# teensyShield1_6_alt.net
KiCad netlist of a schematic drawn in EAGLE
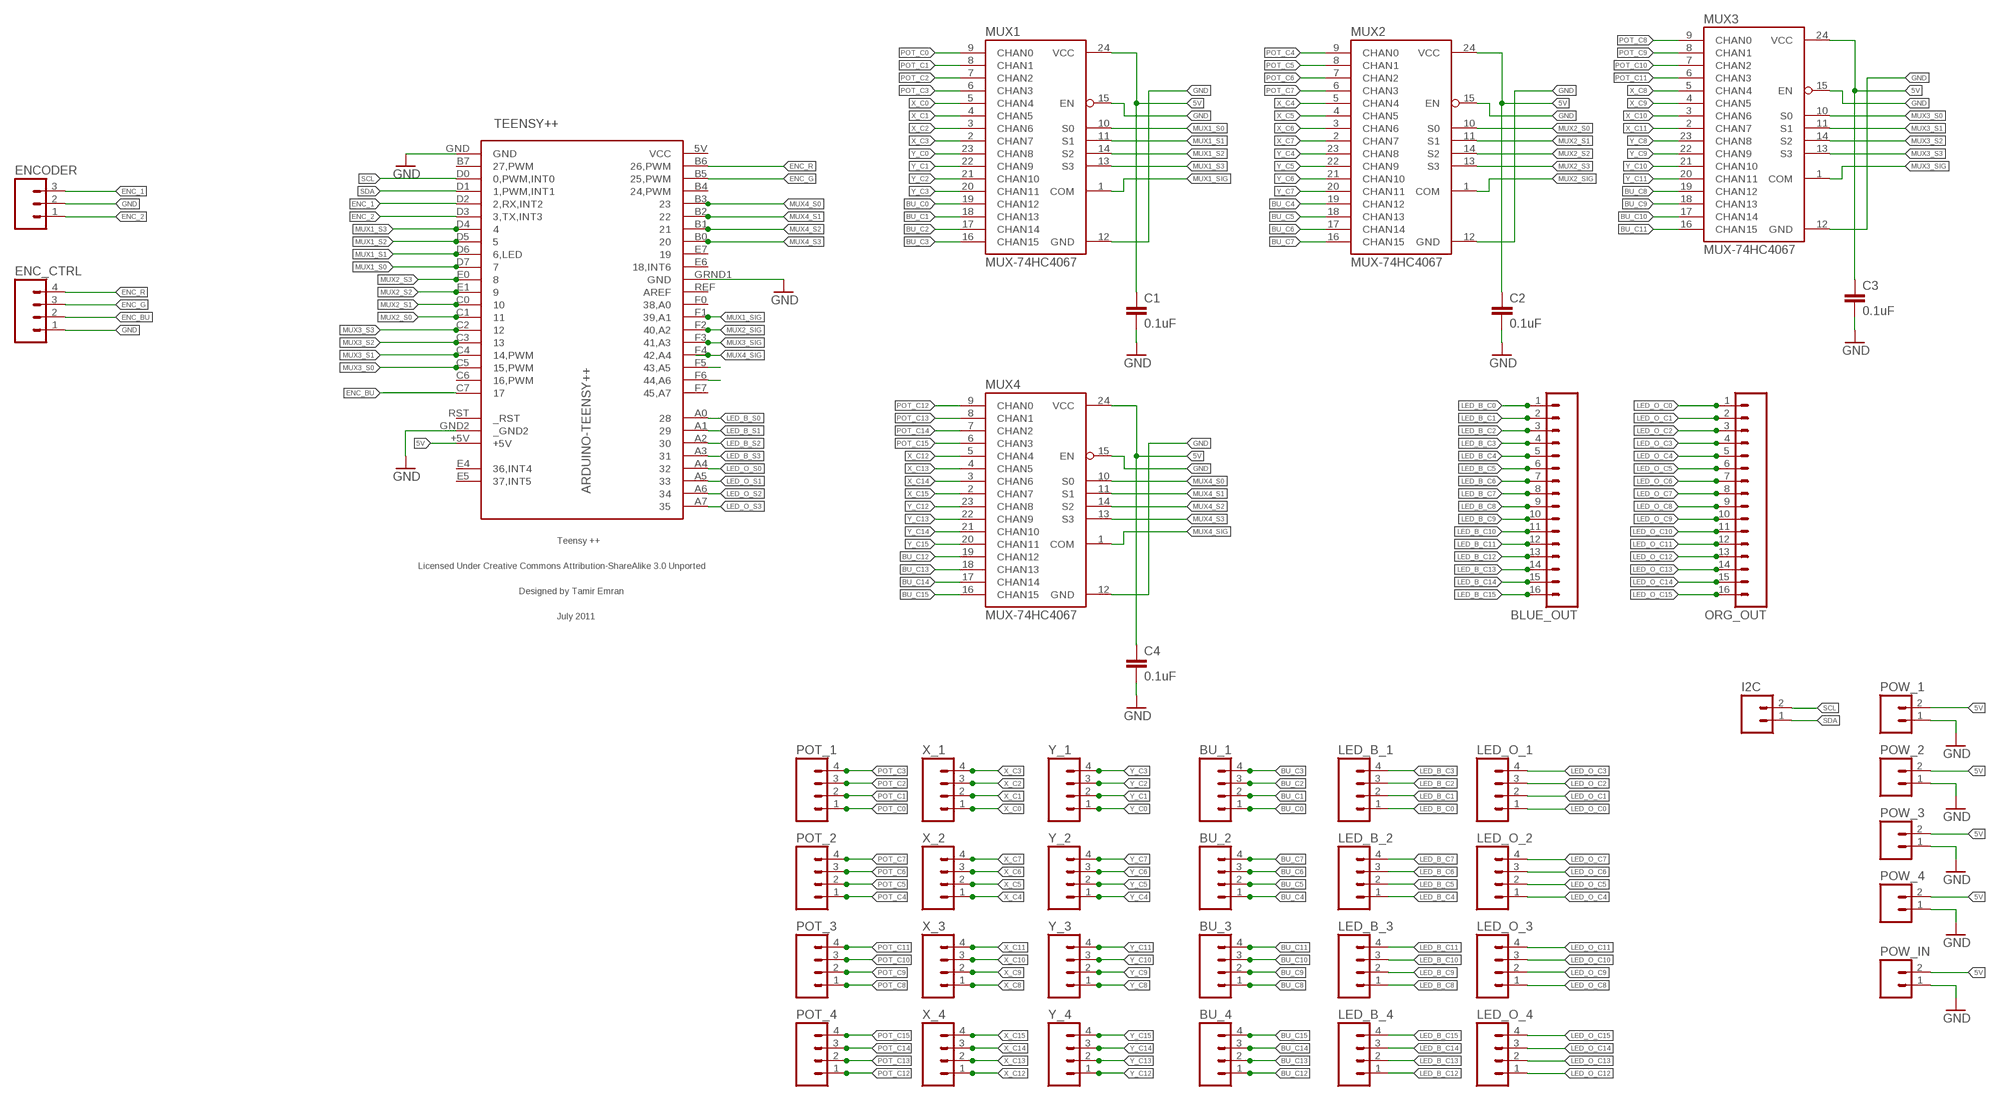
[diagram p0: schematic, sheet 1]

(export (version "E")
  (design (tool "Eeschema 10.0.6"))
  (components
    (comp (ref "BLUE_OUT")
      (value "M161X16_NO_SILK")
      (footprint "eagle-import:1X16_NO_SILK")
      (libsource (lib "eagle-import") (part "M161X16_NO_SILK"))
    )
    (comp (ref "BU_1")
      (value "M04NO_SILK_ALL_ROUND")
      (footprint "eagle-import:1X04_NO_SILK_ALL_ROUND")
      (libsource (lib "eagle-import") (part "M04NO_SILK_ALL_ROUND"))
    )
    (comp (ref "BU_2")
      (value "M04NO_SILK_ALL_ROUND")
      (footprint "eagle-import:1X04_NO_SILK_ALL_ROUND")
      (libsource (lib "eagle-import") (part "M04NO_SILK_ALL_ROUND"))
    )
    (comp (ref "BU_3")
      (value "M04NO_SILK_ALL_ROUND")
      (footprint "eagle-import:1X04_NO_SILK_ALL_ROUND")
      (libsource (lib "eagle-import") (part "M04NO_SILK_ALL_ROUND"))
    )
    (comp (ref "BU_4")
      (value "M04NO_SILK_ALL_ROUND")
      (footprint "eagle-import:1X04_NO_SILK_ALL_ROUND")
      (libsource (lib "eagle-import") (part "M04NO_SILK_ALL_ROUND"))
    )
    (comp (ref "C1")
      (value "0.1uF")
      (footprint "eagle-import:0603")
      (libsource (lib "eagle-import") (part "CAP0603"))
    )
    (comp (ref "C2")
      (value "0.1uF")
      (footprint "eagle-import:0603")
      (libsource (lib "eagle-import") (part "CAP0603"))
    )
    (comp (ref "C3")
      (value "0.1uF")
      (footprint "eagle-import:0603")
      (libsource (lib "eagle-import") (part "CAP0603"))
    )
    (comp (ref "C4")
      (value "0.1uF")
      (footprint "eagle-import:0603")
      (libsource (lib "eagle-import") (part "CAP0603"))
    )
    (comp (ref "ENCODER")
      (value "M031X03_NO_SILK")
      (footprint "eagle-import:1X03_NO_SILK")
      (libsource (lib "eagle-import") (part "M031X03_NO_SILK"))
    )
    (comp (ref "ENC_CTRL")
      (value "M041X04_NO_SILK")
      (footprint "eagle-import:1X04_NO_SILK")
      (libsource (lib "eagle-import") (part "M041X04_NO_SILK"))
    )
    (comp (ref "I2C")
      (value "M02LOCK")
      (footprint "eagle-import:1X02_LOCK")
      (libsource (lib "eagle-import") (part "M02LOCK"))
    )
    (comp (ref "LED_B_1")
      (value "M04NO_SILK_ALL_ROUND")
      (footprint "eagle-import:1X04_NO_SILK_ALL_ROUND")
      (libsource (lib "eagle-import") (part "M04NO_SILK_ALL_ROUND"))
    )
    (comp (ref "LED_B_2")
      (value "M04NO_SILK_ALL_ROUND")
      (footprint "eagle-import:1X04_NO_SILK_ALL_ROUND")
      (libsource (lib "eagle-import") (part "M04NO_SILK_ALL_ROUND"))
    )
    (comp (ref "LED_B_3")
      (value "M04NO_SILK_ALL_ROUND")
      (footprint "eagle-import:1X04_NO_SILK_ALL_ROUND")
      (libsource (lib "eagle-import") (part "M04NO_SILK_ALL_ROUND"))
    )
    (comp (ref "LED_B_4")
      (value "M04NO_SILK_ALL_ROUND")
      (footprint "eagle-import:1X04_NO_SILK_ALL_ROUND")
      (libsource (lib "eagle-import") (part "M04NO_SILK_ALL_ROUND"))
    )
    (comp (ref "LED_O_1")
      (value "M04NO_SILK_ALL_ROUND")
      (footprint "eagle-import:1X04_NO_SILK_ALL_ROUND")
      (libsource (lib "eagle-import") (part "M04NO_SILK_ALL_ROUND"))
    )
    (comp (ref "LED_O_2")
      (value "M04NO_SILK_ALL_ROUND")
      (footprint "eagle-import:1X04_NO_SILK_ALL_ROUND")
      (libsource (lib "eagle-import") (part "M04NO_SILK_ALL_ROUND"))
    )
    (comp (ref "LED_O_3")
      (value "M04NO_SILK_ALL_ROUND")
      (footprint "eagle-import:1X04_NO_SILK_ALL_ROUND")
      (libsource (lib "eagle-import") (part "M04NO_SILK_ALL_ROUND"))
    )
    (comp (ref "LED_O_4")
      (value "M04NO_SILK_ALL_ROUND")
      (footprint "eagle-import:1X04_NO_SILK_ALL_ROUND")
      (libsource (lib "eagle-import") (part "M04NO_SILK_ALL_ROUND"))
    )
    (comp (ref "MUX1")
      (value "MUX-74HC4067")
      (footprint "eagle-import:SSOP24")
      (libsource (lib "eagle-import") (part "MUX-74HC4067SMD"))
    )
    (comp (ref "MUX2")
      (value "MUX-74HC4067")
      (footprint "eagle-import:SSOP24")
      (libsource (lib "eagle-import") (part "MUX-74HC4067SMD"))
    )
    (comp (ref "MUX3")
      (value "MUX-74HC4067")
      (footprint "eagle-import:SSOP24")
      (libsource (lib "eagle-import") (part "MUX-74HC4067SMD"))
    )
    (comp (ref "MUX4")
      (value "MUX-74HC4067")
      (footprint "eagle-import:SSOP24")
      (libsource (lib "eagle-import") (part "MUX-74HC4067SMD"))
    )
    (comp (ref "ORG_OUT")
      (value "M161X16_NO_SILK")
      (footprint "eagle-import:1X16_NO_SILK")
      (libsource (lib "eagle-import") (part "M161X16_NO_SILK"))
    )
    (comp (ref "POT_1")
      (value "M04NO_SILK_ALL_ROUND")
      (footprint "eagle-import:1X04_NO_SILK_ALL_ROUND")
      (libsource (lib "eagle-import") (part "M04NO_SILK_ALL_ROUND"))
    )
    (comp (ref "POT_2")
      (value "M04NO_SILK_ALL_ROUND")
      (footprint "eagle-import:1X04_NO_SILK_ALL_ROUND")
      (libsource (lib "eagle-import") (part "M04NO_SILK_ALL_ROUND"))
    )
    (comp (ref "POT_3")
      (value "M04NO_SILK_ALL_ROUND")
      (footprint "eagle-import:1X04_NO_SILK_ALL_ROUND")
      (libsource (lib "eagle-import") (part "M04NO_SILK_ALL_ROUND"))
    )
    (comp (ref "POT_4")
      (value "M04NO_SILK_ALL_ROUND")
      (footprint "eagle-import:1X04_NO_SILK_ALL_ROUND")
      (libsource (lib "eagle-import") (part "M04NO_SILK_ALL_ROUND"))
    )
    (comp (ref "POW_1")
      (value "M02POLAR")
      (footprint "eagle-import:MOLEX-1X2")
      (libsource (lib "eagle-import") (part "M02POLAR"))
    )
    (comp (ref "POW_2")
      (value "M02POLAR")
      (footprint "eagle-import:MOLEX-1X2")
      (libsource (lib "eagle-import") (part "M02POLAR"))
    )
    (comp (ref "POW_3")
      (value "M02POLAR")
      (footprint "eagle-import:MOLEX-1X2")
      (libsource (lib "eagle-import") (part "M02POLAR"))
    )
    (comp (ref "POW_4")
      (value "M02POLAR")
      (footprint "eagle-import:MOLEX-1X2")
      (libsource (lib "eagle-import") (part "M02POLAR"))
    )
    (comp (ref "POW_IN")
      (value "M02POLAR")
      (footprint "eagle-import:MOLEX-1X2")
      (libsource (lib "eagle-import") (part "M02POLAR"))
    )
    (comp (ref "TEENSY++")
      (value "ARDUINO-TEENSY++")
      (footprint "eagle-import:TEENSY++")
      (libsource (lib "eagle-import") (part "ARDUINO-TEENSY++"))
    )
    (comp (ref "X_1")
      (value "M04NO_SILK_ALL_ROUND")
      (footprint "eagle-import:1X04_NO_SILK_ALL_ROUND")
      (libsource (lib "eagle-import") (part "M04NO_SILK_ALL_ROUND"))
    )
    (comp (ref "X_2")
      (value "M04NO_SILK_ALL_ROUND")
      (footprint "eagle-import:1X04_NO_SILK_ALL_ROUND")
      (libsource (lib "eagle-import") (part "M04NO_SILK_ALL_ROUND"))
    )
    (comp (ref "X_3")
      (value "M04NO_SILK_ALL_ROUND")
      (footprint "eagle-import:1X04_NO_SILK_ALL_ROUND")
      (libsource (lib "eagle-import") (part "M04NO_SILK_ALL_ROUND"))
    )
    (comp (ref "X_4")
      (value "M04NO_SILK_ALL_ROUND")
      (footprint "eagle-import:1X04_NO_SILK_ALL_ROUND")
      (libsource (lib "eagle-import") (part "M04NO_SILK_ALL_ROUND"))
    )
    (comp (ref "Y_1")
      (value "M04NO_SILK_ALL_ROUND")
      (footprint "eagle-import:1X04_NO_SILK_ALL_ROUND")
      (libsource (lib "eagle-import") (part "M04NO_SILK_ALL_ROUND"))
    )
    (comp (ref "Y_2")
      (value "M04NO_SILK_ALL_ROUND")
      (footprint "eagle-import:1X04_NO_SILK_ALL_ROUND")
      (libsource (lib "eagle-import") (part "M04NO_SILK_ALL_ROUND"))
    )
    (comp (ref "Y_3")
      (value "M04NO_SILK_ALL_ROUND")
      (footprint "eagle-import:1X04_NO_SILK_ALL_ROUND")
      (libsource (lib "eagle-import") (part "M04NO_SILK_ALL_ROUND"))
    )
    (comp (ref "Y_4")
      (value "M04NO_SILK_ALL_ROUND")
      (footprint "eagle-import:1X04_NO_SILK_ALL_ROUND")
      (libsource (lib "eagle-import") (part "M04NO_SILK_ALL_ROUND"))
    )
  )
  (nets
    (net (code "1") (name "/VCC") (class "Default")
      (node (ref "TEENSY++") (pin "5V") (pinfunction "VCC_5V") (pintype "power_in"))
    )
    (net (code "2") (name "5V") (class "Default")
      (node (ref "C1") (pin "1") (pinfunction "1_1") (pintype "passive"))
      (node (ref "C2") (pin "1") (pinfunction "1_1") (pintype "passive"))
      (node (ref "C3") (pin "1") (pinfunction "1_1") (pintype "passive"))
      (node (ref "C4") (pin "1") (pinfunction "1_1") (pintype "passive"))
      (node (ref "MUX1") (pin "24") (pinfunction "VCC_24") (pintype "bidirectional"))
      (node (ref "MUX2") (pin "24") (pinfunction "VCC_24") (pintype "bidirectional"))
      (node (ref "MUX3") (pin "24") (pinfunction "VCC_24") (pintype "bidirectional"))
      (node (ref "MUX4") (pin "24") (pinfunction "VCC_24") (pintype "bidirectional"))
      (node (ref "POW_1") (pin "2") (pinfunction "2_2") (pintype "passive"))
      (node (ref "POW_2") (pin "2") (pinfunction "2_2") (pintype "passive"))
      (node (ref "POW_3") (pin "2") (pinfunction "2_2") (pintype "passive"))
      (node (ref "POW_4") (pin "2") (pinfunction "2_2") (pintype "passive"))
      (node (ref "POW_IN") (pin "2") (pinfunction "2_2") (pintype "passive"))
    )
    (net (code "3") (name "BU_C0") (class "Default")
      (node (ref "BU_1") (pin "1") (pinfunction "1_1") (pintype "passive"))
      (node (ref "MUX1") (pin "19") (pinfunction "CHAN12_19") (pintype "bidirectional"))
    )
    (net (code "4") (name "BU_C1") (class "Default")
      (node (ref "BU_1") (pin "2") (pinfunction "2_2") (pintype "passive"))
      (node (ref "MUX1") (pin "18") (pinfunction "CHAN13_18") (pintype "bidirectional"))
    )
    (net (code "5") (name "BU_C2") (class "Default")
      (node (ref "BU_1") (pin "3") (pinfunction "3_3") (pintype "passive"))
      (node (ref "MUX1") (pin "17") (pinfunction "CHAN14_17") (pintype "bidirectional"))
    )
    (net (code "6") (name "BU_C3") (class "Default")
      (node (ref "BU_1") (pin "4") (pinfunction "4_4") (pintype "passive"))
      (node (ref "MUX1") (pin "16") (pinfunction "CHAN15_16") (pintype "bidirectional"))
    )
    (net (code "7") (name "BU_C4") (class "Default")
      (node (ref "BU_2") (pin "1") (pinfunction "1_1") (pintype "passive"))
      (node (ref "MUX2") (pin "19") (pinfunction "CHAN12_19") (pintype "bidirectional"))
    )
    (net (code "8") (name "BU_C5") (class "Default")
      (node (ref "BU_2") (pin "2") (pinfunction "2_2") (pintype "passive"))
      (node (ref "MUX2") (pin "18") (pinfunction "CHAN13_18") (pintype "bidirectional"))
    )
    (net (code "9") (name "BU_C6") (class "Default")
      (node (ref "BU_2") (pin "3") (pinfunction "3_3") (pintype "passive"))
      (node (ref "MUX2") (pin "17") (pinfunction "CHAN14_17") (pintype "bidirectional"))
    )
    (net (code "10") (name "BU_C7") (class "Default")
      (node (ref "BU_2") (pin "4") (pinfunction "4_4") (pintype "passive"))
      (node (ref "MUX2") (pin "16") (pinfunction "CHAN15_16") (pintype "bidirectional"))
    )
    (net (code "11") (name "BU_C8") (class "Default")
      (node (ref "BU_3") (pin "1") (pinfunction "1_1") (pintype "passive"))
      (node (ref "MUX3") (pin "19") (pinfunction "CHAN12_19") (pintype "bidirectional"))
    )
    (net (code "12") (name "BU_C9") (class "Default")
      (node (ref "BU_3") (pin "2") (pinfunction "2_2") (pintype "passive"))
      (node (ref "MUX3") (pin "18") (pinfunction "CHAN13_18") (pintype "bidirectional"))
    )
    (net (code "13") (name "BU_C10") (class "Default")
      (node (ref "BU_3") (pin "3") (pinfunction "3_3") (pintype "passive"))
      (node (ref "MUX3") (pin "17") (pinfunction "CHAN14_17") (pintype "bidirectional"))
    )
    (net (code "14") (name "BU_C11") (class "Default")
      (node (ref "BU_3") (pin "4") (pinfunction "4_4") (pintype "passive"))
      (node (ref "MUX3") (pin "16") (pinfunction "CHAN15_16") (pintype "bidirectional"))
    )
    (net (code "15") (name "BU_C12") (class "Default")
      (node (ref "BU_4") (pin "1") (pinfunction "1_1") (pintype "passive"))
      (node (ref "MUX4") (pin "19") (pinfunction "CHAN12_19") (pintype "bidirectional"))
    )
    (net (code "16") (name "BU_C13") (class "Default")
      (node (ref "BU_4") (pin "2") (pinfunction "2_2") (pintype "passive"))
      (node (ref "MUX4") (pin "18") (pinfunction "CHAN13_18") (pintype "bidirectional"))
    )
    (net (code "17") (name "BU_C14") (class "Default")
      (node (ref "BU_4") (pin "3") (pinfunction "3_3") (pintype "passive"))
      (node (ref "MUX4") (pin "17") (pinfunction "CHAN14_17") (pintype "bidirectional"))
    )
    (net (code "18") (name "BU_C15") (class "Default")
      (node (ref "BU_4") (pin "4") (pinfunction "4_4") (pintype "passive"))
      (node (ref "MUX4") (pin "16") (pinfunction "CHAN15_16") (pintype "bidirectional"))
    )
    (net (code "19") (name "ENC_1") (class "Default")
      (node (ref "ENCODER") (pin "3") (pinfunction "3_3") (pintype "passive"))
      (node (ref "TEENSY++") (pin "D2") (pinfunction "2,RX,INT2_D2") (pintype "bidirectional"))
    )
    (net (code "20") (name "ENC_2") (class "Default")
      (node (ref "ENCODER") (pin "1") (pinfunction "1_1") (pintype "passive"))
      (node (ref "TEENSY++") (pin "D3") (pinfunction "3,TX,INT3_D3") (pintype "bidirectional"))
    )
    (net (code "21") (name "ENC_BU") (class "Default")
      (node (ref "ENC_CTRL") (pin "2") (pinfunction "2_2") (pintype "passive"))
      (node (ref "TEENSY++") (pin "C7") (pinfunction "17_C7") (pintype "bidirectional"))
    )
    (net (code "22") (name "ENC_G") (class "Default")
      (node (ref "ENC_CTRL") (pin "3") (pinfunction "3_3") (pintype "passive"))
      (node (ref "TEENSY++") (pin "B5") (pinfunction "25,PWM_B5") (pintype "bidirectional"))
    )
    (net (code "23") (name "ENC_R") (class "Default")
      (node (ref "ENC_CTRL") (pin "4") (pinfunction "4_4") (pintype "passive"))
      (node (ref "TEENSY++") (pin "B6") (pinfunction "26,PWM_B6") (pintype "bidirectional"))
    )
    (net (code "24") (name "GND") (class "Default")
      (node (ref "C1") (pin "2") (pinfunction "2_2") (pintype "passive"))
      (node (ref "C2") (pin "2") (pinfunction "2_2") (pintype "passive"))
      (node (ref "C3") (pin "2") (pinfunction "2_2") (pintype "passive"))
      (node (ref "C4") (pin "2") (pinfunction "2_2") (pintype "passive"))
      (node (ref "ENCODER") (pin "2") (pinfunction "2_2") (pintype "passive"))
      (node (ref "ENC_CTRL") (pin "1") (pinfunction "1_1") (pintype "passive"))
      (node (ref "MUX1") (pin "12") (pinfunction "GND_12") (pintype "bidirectional"))
      (node (ref "MUX1") (pin "15") (pinfunction "EN_15") (pintype "input"))
      (node (ref "MUX2") (pin "12") (pinfunction "GND_12") (pintype "bidirectional"))
      (node (ref "MUX2") (pin "15") (pinfunction "EN_15") (pintype "input"))
      (node (ref "MUX3") (pin "12") (pinfunction "GND_12") (pintype "bidirectional"))
      (node (ref "MUX3") (pin "15") (pinfunction "EN_15") (pintype "input"))
      (node (ref "MUX4") (pin "12") (pinfunction "GND_12") (pintype "bidirectional"))
      (node (ref "MUX4") (pin "15") (pinfunction "EN_15") (pintype "input"))
      (node (ref "POW_1") (pin "1") (pinfunction "1_1") (pintype "passive"))
      (node (ref "POW_2") (pin "1") (pinfunction "1_1") (pintype "passive"))
      (node (ref "POW_3") (pin "1") (pinfunction "1_1") (pintype "passive"))
      (node (ref "POW_4") (pin "1") (pinfunction "1_1") (pintype "passive"))
      (node (ref "POW_IN") (pin "1") (pinfunction "1_1") (pintype "passive"))
      (node (ref "TEENSY++") (pin "GND") (pinfunction "GND_GND") (pintype "power_in"))
      (node (ref "TEENSY++") (pin "GND2") (pinfunction "_GND2_GND2") (pintype "power_in"))
      (node (ref "TEENSY++") (pin "GRND1") (pinfunction "GND_GRND1") (pintype "power_in"))
    )
    (net (code "25") (name "LED_B_C0") (class "Default")
      (node (ref "BLUE_OUT") (pin "1") (pinfunction "1_1") (pintype "passive"))
      (node (ref "LED_B_1") (pin "1") (pinfunction "1_1") (pintype "passive"))
    )
    (net (code "26") (name "LED_B_C1") (class "Default")
      (node (ref "BLUE_OUT") (pin "2") (pinfunction "2_2") (pintype "passive"))
      (node (ref "LED_B_1") (pin "2") (pinfunction "2_2") (pintype "passive"))
    )
    (net (code "27") (name "LED_B_C2") (class "Default")
      (node (ref "BLUE_OUT") (pin "3") (pinfunction "3_3") (pintype "passive"))
      (node (ref "LED_B_1") (pin "3") (pinfunction "3_3") (pintype "passive"))
    )
    (net (code "28") (name "LED_B_C3") (class "Default")
      (node (ref "BLUE_OUT") (pin "4") (pinfunction "4_4") (pintype "passive"))
      (node (ref "LED_B_1") (pin "4") (pinfunction "4_4") (pintype "passive"))
    )
    (net (code "29") (name "LED_B_C4") (class "Default")
      (node (ref "BLUE_OUT") (pin "5") (pinfunction "5_5") (pintype "passive"))
      (node (ref "LED_B_2") (pin "1") (pinfunction "1_1") (pintype "passive"))
    )
    (net (code "30") (name "LED_B_C5") (class "Default")
      (node (ref "BLUE_OUT") (pin "6") (pinfunction "6_6") (pintype "passive"))
      (node (ref "LED_B_2") (pin "2") (pinfunction "2_2") (pintype "passive"))
    )
    (net (code "31") (name "LED_B_C6") (class "Default")
      (node (ref "BLUE_OUT") (pin "7") (pinfunction "7_7") (pintype "passive"))
      (node (ref "LED_B_2") (pin "3") (pinfunction "3_3") (pintype "passive"))
    )
    (net (code "32") (name "LED_B_C7") (class "Default")
      (node (ref "BLUE_OUT") (pin "8") (pinfunction "8_8") (pintype "passive"))
      (node (ref "LED_B_2") (pin "4") (pinfunction "4_4") (pintype "passive"))
    )
    (net (code "33") (name "LED_B_C8") (class "Default")
      (node (ref "BLUE_OUT") (pin "9") (pinfunction "9_9") (pintype "passive"))
      (node (ref "LED_B_3") (pin "1") (pinfunction "1_1") (pintype "passive"))
    )
    (net (code "34") (name "LED_B_C9") (class "Default")
      (node (ref "BLUE_OUT") (pin "10") (pinfunction "10_10") (pintype "passive"))
      (node (ref "LED_B_3") (pin "2") (pinfunction "2_2") (pintype "passive"))
    )
    (net (code "35") (name "LED_B_C10") (class "Default")
      (node (ref "BLUE_OUT") (pin "11") (pinfunction "11_11") (pintype "passive"))
      (node (ref "LED_B_3") (pin "3") (pinfunction "3_3") (pintype "passive"))
    )
    (net (code "36") (name "LED_B_C11") (class "Default")
      (node (ref "BLUE_OUT") (pin "12") (pinfunction "12_12") (pintype "passive"))
      (node (ref "LED_B_3") (pin "4") (pinfunction "4_4") (pintype "passive"))
    )
    (net (code "37") (name "LED_B_C12") (class "Default")
      (node (ref "BLUE_OUT") (pin "13") (pinfunction "13_13") (pintype "passive"))
      (node (ref "LED_B_4") (pin "1") (pinfunction "1_1") (pintype "passive"))
    )
    (net (code "38") (name "LED_B_C13") (class "Default")
      (node (ref "BLUE_OUT") (pin "14") (pinfunction "14_14") (pintype "passive"))
      (node (ref "LED_B_4") (pin "2") (pinfunction "2_2") (pintype "passive"))
    )
    (net (code "39") (name "LED_B_C14") (class "Default")
      (node (ref "BLUE_OUT") (pin "15") (pinfunction "15_15") (pintype "passive"))
      (node (ref "LED_B_4") (pin "3") (pinfunction "3_3") (pintype "passive"))
    )
    (net (code "40") (name "LED_B_C15") (class "Default")
      (node (ref "BLUE_OUT") (pin "16") (pinfunction "16_16") (pintype "passive"))
      (node (ref "LED_B_4") (pin "4") (pinfunction "4_4") (pintype "passive"))
    )
    (net (code "41") (name "LED_B_S0") (class "Default")
      (node (ref "TEENSY++") (pin "A0") (pinfunction "28_A0") (pintype "bidirectional"))
    )
    (net (code "42") (name "LED_B_S1") (class "Default")
      (node (ref "TEENSY++") (pin "A1") (pinfunction "29_A1") (pintype "bidirectional"))
    )
    (net (code "43") (name "LED_B_S2") (class "Default")
      (node (ref "TEENSY++") (pin "A2") (pinfunction "30_A2") (pintype "bidirectional"))
    )
    (net (code "44") (name "LED_B_S3") (class "Default")
      (node (ref "TEENSY++") (pin "A3") (pinfunction "31_A3") (pintype "bidirectional"))
    )
    (net (code "45") (name "LED_O_C0") (class "Default")
      (node (ref "LED_O_1") (pin "1") (pinfunction "1_1") (pintype "passive"))
      (node (ref "ORG_OUT") (pin "1") (pinfunction "1_1") (pintype "passive"))
    )
    (net (code "46") (name "LED_O_C1") (class "Default")
      (node (ref "LED_O_1") (pin "2") (pinfunction "2_2") (pintype "passive"))
      (node (ref "ORG_OUT") (pin "2") (pinfunction "2_2") (pintype "passive"))
    )
    (net (code "47") (name "LED_O_C2") (class "Default")
      (node (ref "LED_O_1") (pin "3") (pinfunction "3_3") (pintype "passive"))
      (node (ref "ORG_OUT") (pin "3") (pinfunction "3_3") (pintype "passive"))
    )
    (net (code "48") (name "LED_O_C3") (class "Default")
      (node (ref "LED_O_1") (pin "4") (pinfunction "4_4") (pintype "passive"))
      (node (ref "ORG_OUT") (pin "4") (pinfunction "4_4") (pintype "passive"))
    )
    (net (code "49") (name "LED_O_C4") (class "Default")
      (node (ref "LED_O_2") (pin "1") (pinfunction "1_1") (pintype "passive"))
      (node (ref "ORG_OUT") (pin "5") (pinfunction "5_5") (pintype "passive"))
    )
    (net (code "50") (name "LED_O_C5") (class "Default")
      (node (ref "LED_O_2") (pin "2") (pinfunction "2_2") (pintype "passive"))
      (node (ref "ORG_OUT") (pin "6") (pinfunction "6_6") (pintype "passive"))
    )
    (net (code "51") (name "LED_O_C6") (class "Default")
      (node (ref "LED_O_2") (pin "3") (pinfunction "3_3") (pintype "passive"))
      (node (ref "ORG_OUT") (pin "7") (pinfunction "7_7") (pintype "passive"))
    )
    (net (code "52") (name "LED_O_C7") (class "Default")
      (node (ref "LED_O_2") (pin "4") (pinfunction "4_4") (pintype "passive"))
      (node (ref "ORG_OUT") (pin "8") (pinfunction "8_8") (pintype "passive"))
    )
    (net (code "53") (name "LED_O_C8") (class "Default")
      (node (ref "LED_O_3") (pin "1") (pinfunction "1_1") (pintype "passive"))
      (node (ref "ORG_OUT") (pin "9") (pinfunction "9_9") (pintype "passive"))
    )
    (net (code "54") (name "LED_O_C9") (class "Default")
      (node (ref "LED_O_3") (pin "2") (pinfunction "2_2") (pintype "passive"))
      (node (ref "ORG_OUT") (pin "10") (pinfunction "10_10") (pintype "passive"))
    )
    (net (code "55") (name "LED_O_C10") (class "Default")
      (node (ref "LED_O_3") (pin "3") (pinfunction "3_3") (pintype "passive"))
      (node (ref "ORG_OUT") (pin "11") (pinfunction "11_11") (pintype "passive"))
    )
    (net (code "56") (name "LED_O_C11") (class "Default")
      (node (ref "LED_O_3") (pin "4") (pinfunction "4_4") (pintype "passive"))
      (node (ref "ORG_OUT") (pin "12") (pinfunction "12_12") (pintype "passive"))
    )
    (net (code "57") (name "LED_O_C12") (class "Default")
      (node (ref "LED_O_4") (pin "1") (pinfunction "1_1") (pintype "passive"))
      (node (ref "ORG_OUT") (pin "13") (pinfunction "13_13") (pintype "passive"))
    )
    (net (code "58") (name "LED_O_C13") (class "Default")
      (node (ref "LED_O_4") (pin "2") (pinfunction "2_2") (pintype "passive"))
      (node (ref "ORG_OUT") (pin "14") (pinfunction "14_14") (pintype "passive"))
    )
    (net (code "59") (name "LED_O_C14") (class "Default")
      (node (ref "LED_O_4") (pin "3") (pinfunction "3_3") (pintype "passive"))
      (node (ref "ORG_OUT") (pin "15") (pinfunction "15_15") (pintype "passive"))
    )
    (net (code "60") (name "LED_O_C15") (class "Default")
      (node (ref "LED_O_4") (pin "4") (pinfunction "4_4") (pintype "passive"))
      (node (ref "ORG_OUT") (pin "16") (pinfunction "16_16") (pintype "passive"))
    )
    (net (code "61") (name "LED_O_S0") (class "Default")
      (node (ref "TEENSY++") (pin "A4") (pinfunction "32_A4") (pintype "bidirectional"))
    )
    (net (code "62") (name "LED_O_S1") (class "Default")
      (node (ref "TEENSY++") (pin "A5") (pinfunction "33_A5") (pintype "bidirectional"))
    )
    (net (code "63") (name "LED_O_S2") (class "Default")
      (node (ref "TEENSY++") (pin "A6") (pinfunction "34_A6") (pintype "bidirectional"))
    )
    (net (code "64") (name "LED_O_S3") (class "Default")
      (node (ref "TEENSY++") (pin "A7") (pinfunction "35_A7") (pintype "bidirectional"))
    )
    (net (code "65") (name "MUX1_S0") (class "Default")
      (node (ref "MUX1") (pin "10") (pinfunction "S0_10") (pintype "input"))
      (node (ref "TEENSY++") (pin "D7") (pinfunction "7_D7") (pintype "bidirectional"))
    )
    (net (code "66") (name "MUX1_S1") (class "Default")
      (node (ref "MUX1") (pin "11") (pinfunction "S1_11") (pintype "input"))
      (node (ref "TEENSY++") (pin "D6") (pinfunction "6,LED_D6") (pintype "bidirectional"))
    )
    (net (code "67") (name "MUX1_S2") (class "Default")
      (node (ref "MUX1") (pin "14") (pinfunction "S2_14") (pintype "input"))
      (node (ref "TEENSY++") (pin "D5") (pinfunction "5_D5") (pintype "bidirectional"))
    )
    (net (code "68") (name "MUX1_S3") (class "Default")
      (node (ref "MUX1") (pin "13") (pinfunction "S3_13") (pintype "input"))
      (node (ref "TEENSY++") (pin "D4") (pinfunction "4_D4") (pintype "bidirectional"))
    )
    (net (code "69") (name "MUX1_SIG") (class "Default")
      (node (ref "MUX1") (pin "1") (pinfunction "COM_1") (pintype "bidirectional"))
    )
    (net (code "70") (name "MUX2_S0") (class "Default")
      (node (ref "MUX2") (pin "10") (pinfunction "S0_10") (pintype "input"))
      (node (ref "TEENSY++") (pin "C1") (pinfunction "11_C1") (pintype "bidirectional"))
    )
    (net (code "71") (name "MUX2_S1") (class "Default")
      (node (ref "MUX2") (pin "11") (pinfunction "S1_11") (pintype "input"))
      (node (ref "TEENSY++") (pin "C0") (pinfunction "10_C0") (pintype "bidirectional"))
    )
    (net (code "72") (name "MUX2_S2") (class "Default")
      (node (ref "MUX2") (pin "14") (pinfunction "S2_14") (pintype "input"))
      (node (ref "TEENSY++") (pin "E1") (pinfunction "9_E1") (pintype "bidirectional"))
    )
    (net (code "73") (name "MUX2_S3") (class "Default")
      (node (ref "MUX2") (pin "13") (pinfunction "S3_13") (pintype "input"))
      (node (ref "TEENSY++") (pin "E0") (pinfunction "8_E0") (pintype "bidirectional"))
    )
    (net (code "74") (name "MUX2_SIG") (class "Default")
      (node (ref "MUX2") (pin "1") (pinfunction "COM_1") (pintype "bidirectional"))
    )
    (net (code "75") (name "MUX3_S0") (class "Default")
      (node (ref "MUX3") (pin "10") (pinfunction "S0_10") (pintype "input"))
      (node (ref "TEENSY++") (pin "C5") (pinfunction "15,PWM_C5") (pintype "bidirectional"))
    )
    (net (code "76") (name "MUX3_S1") (class "Default")
      (node (ref "MUX3") (pin "11") (pinfunction "S1_11") (pintype "input"))
      (node (ref "TEENSY++") (pin "C4") (pinfunction "14,PWM_C4") (pintype "bidirectional"))
    )
    (net (code "77") (name "MUX3_S2") (class "Default")
      (node (ref "MUX3") (pin "14") (pinfunction "S2_14") (pintype "input"))
      (node (ref "TEENSY++") (pin "C3") (pinfunction "13_C3") (pintype "bidirectional"))
    )
    (net (code "78") (name "MUX3_S3") (class "Default")
      (node (ref "MUX3") (pin "13") (pinfunction "S3_13") (pintype "input"))
      (node (ref "TEENSY++") (pin "C2") (pinfunction "12_C2") (pintype "bidirectional"))
    )
    (net (code "79") (name "MUX3_SIG") (class "Default")
      (node (ref "MUX3") (pin "1") (pinfunction "COM_1") (pintype "bidirectional"))
      (node (ref "TEENSY++") (pin "F3") (pinfunction "41,A3_F3") (pintype "bidirectional"))
    )
    (net (code "80") (name "MUX4_S0") (class "Default")
      (node (ref "MUX4") (pin "10") (pinfunction "S0_10") (pintype "input"))
      (node (ref "TEENSY++") (pin "B3") (pinfunction "23_B3") (pintype "bidirectional"))
    )
    (net (code "81") (name "MUX4_S1") (class "Default")
      (node (ref "MUX4") (pin "11") (pinfunction "S1_11") (pintype "input"))
      (node (ref "TEENSY++") (pin "B2") (pinfunction "22_B2") (pintype "bidirectional"))
    )
    (net (code "82") (name "MUX4_S2") (class "Default")
      (node (ref "MUX4") (pin "14") (pinfunction "S2_14") (pintype "input"))
      (node (ref "TEENSY++") (pin "B1") (pinfunction "21_B1") (pintype "bidirectional"))
    )
    (net (code "83") (name "MUX4_S3") (class "Default")
      (node (ref "MUX4") (pin "13") (pinfunction "S3_13") (pintype "input"))
      (node (ref "TEENSY++") (pin "B0") (pinfunction "20_B0") (pintype "bidirectional"))
    )
    (net (code "84") (name "MUX4_SIG") (class "Default")
      (node (ref "MUX4") (pin "1") (pinfunction "COM_1") (pintype "bidirectional"))
      (node (ref "TEENSY++") (pin "F4") (pinfunction "42,A4_F4") (pintype "bidirectional"))
    )
    (net (code "85") (name "POT_C0") (class "Default")
      (node (ref "MUX1") (pin "9") (pinfunction "CHAN0_9") (pintype "bidirectional"))
      (node (ref "POT_1") (pin "1") (pinfunction "1_1") (pintype "passive"))
    )
    (net (code "86") (name "POT_C1") (class "Default")
      (node (ref "MUX1") (pin "8") (pinfunction "CHAN1_8") (pintype "bidirectional"))
      (node (ref "POT_1") (pin "2") (pinfunction "2_2") (pintype "passive"))
    )
    (net (code "87") (name "POT_C2") (class "Default")
      (node (ref "MUX1") (pin "7") (pinfunction "CHAN2_7") (pintype "bidirectional"))
      (node (ref "POT_1") (pin "3") (pinfunction "3_3") (pintype "passive"))
    )
    (net (code "88") (name "POT_C3") (class "Default")
      (node (ref "MUX1") (pin "6") (pinfunction "CHAN3_6") (pintype "bidirectional"))
      (node (ref "POT_1") (pin "4") (pinfunction "4_4") (pintype "passive"))
    )
    (net (code "89") (name "POT_C4") (class "Default")
      (node (ref "MUX2") (pin "9") (pinfunction "CHAN0_9") (pintype "bidirectional"))
      (node (ref "POT_2") (pin "1") (pinfunction "1_1") (pintype "passive"))
    )
    (net (code "90") (name "POT_C5") (class "Default")
      (node (ref "MUX2") (pin "8") (pinfunction "CHAN1_8") (pintype "bidirectional"))
      (node (ref "POT_2") (pin "2") (pinfunction "2_2") (pintype "passive"))
    )
    (net (code "91") (name "POT_C6") (class "Default")
      (node (ref "MUX2") (pin "7") (pinfunction "CHAN2_7") (pintype "bidirectional"))
      (node (ref "POT_2") (pin "3") (pinfunction "3_3") (pintype "passive"))
    )
    (net (code "92") (name "POT_C7") (class "Default")
      (node (ref "MUX2") (pin "6") (pinfunction "CHAN3_6") (pintype "bidirectional"))
      (node (ref "POT_2") (pin "4") (pinfunction "4_4") (pintype "passive"))
    )
    (net (code "93") (name "POT_C8") (class "Default")
      (node (ref "MUX3") (pin "9") (pinfunction "CHAN0_9") (pintype "bidirectional"))
      (node (ref "POT_3") (pin "1") (pinfunction "1_1") (pintype "passive"))
    )
    (net (code "94") (name "POT_C9") (class "Default")
      (node (ref "MUX3") (pin "8") (pinfunction "CHAN1_8") (pintype "bidirectional"))
      (node (ref "POT_3") (pin "2") (pinfunction "2_2") (pintype "passive"))
    )
    (net (code "95") (name "POT_C10") (class "Default")
      (node (ref "MUX3") (pin "7") (pinfunction "CHAN2_7") (pintype "bidirectional"))
      (node (ref "POT_3") (pin "3") (pinfunction "3_3") (pintype "passive"))
    )
    (net (code "96") (name "POT_C11") (class "Default")
      (node (ref "MUX3") (pin "6") (pinfunction "CHAN3_6") (pintype "bidirectional"))
      (node (ref "POT_3") (pin "4") (pinfunction "4_4") (pintype "passive"))
    )
    (net (code "97") (name "POT_C12") (class "Default")
      (node (ref "MUX4") (pin "9") (pinfunction "CHAN0_9") (pintype "bidirectional"))
      (node (ref "POT_4") (pin "1") (pinfunction "1_1") (pintype "passive"))
    )
    (net (code "98") (name "POT_C13") (class "Default")
      (node (ref "MUX4") (pin "8") (pinfunction "CHAN1_8") (pintype "bidirectional"))
      (node (ref "POT_4") (pin "2") (pinfunction "2_2") (pintype "passive"))
    )
    (net (code "99") (name "POT_C14") (class "Default")
      (node (ref "MUX4") (pin "7") (pinfunction "CHAN2_7") (pintype "bidirectional"))
      (node (ref "POT_4") (pin "3") (pinfunction "3_3") (pintype "passive"))
    )
    (net (code "100") (name "POT_C15") (class "Default")
      (node (ref "MUX4") (pin "6") (pinfunction "CHAN3_6") (pintype "bidirectional"))
      (node (ref "POT_4") (pin "4") (pinfunction "4_4") (pintype "passive"))
    )
    (net (code "101") (name "SCL") (class "Default")
      (node (ref "I2C") (pin "2") (pinfunction "2_2") (pintype "passive"))
      (node (ref "TEENSY++") (pin "D0") (pinfunction "0,PWM,INT0_D0") (pintype "bidirectional"))
    )
    (net (code "102") (name "SDA") (class "Default")
      (node (ref "I2C") (pin "1") (pinfunction "1_1") (pintype "passive"))
      (node (ref "TEENSY++") (pin "D1") (pinfunction "1,PWM,INT1_D1") (pintype "bidirectional"))
    )
    (net (code "103") (name "X_C0") (class "Default")
      (node (ref "MUX1") (pin "5") (pinfunction "CHAN4_5") (pintype "bidirectional"))
      (node (ref "X_1") (pin "1") (pinfunction "1_1") (pintype "passive"))
    )
    (net (code "104") (name "X_C1") (class "Default")
      (node (ref "MUX1") (pin "4") (pinfunction "CHAN5_4") (pintype "bidirectional"))
      (node (ref "X_1") (pin "2") (pinfunction "2_2") (pintype "passive"))
    )
    (net (code "105") (name "X_C2") (class "Default")
      (node (ref "MUX1") (pin "3") (pinfunction "CHAN6_3") (pintype "bidirectional"))
      (node (ref "X_1") (pin "3") (pinfunction "3_3") (pintype "passive"))
    )
    (net (code "106") (name "X_C3") (class "Default")
      (node (ref "MUX1") (pin "2") (pinfunction "CHAN7_2") (pintype "bidirectional"))
      (node (ref "X_1") (pin "4") (pinfunction "4_4") (pintype "passive"))
    )
    (net (code "107") (name "X_C4") (class "Default")
      (node (ref "MUX2") (pin "5") (pinfunction "CHAN4_5") (pintype "bidirectional"))
      (node (ref "X_2") (pin "1") (pinfunction "1_1") (pintype "passive"))
    )
    (net (code "108") (name "X_C5") (class "Default")
      (node (ref "MUX2") (pin "4") (pinfunction "CHAN5_4") (pintype "bidirectional"))
      (node (ref "X_2") (pin "2") (pinfunction "2_2") (pintype "passive"))
    )
    (net (code "109") (name "X_C6") (class "Default")
      (node (ref "MUX2") (pin "3") (pinfunction "CHAN6_3") (pintype "bidirectional"))
      (node (ref "X_2") (pin "3") (pinfunction "3_3") (pintype "passive"))
    )
    (net (code "110") (name "X_C7") (class "Default")
      (node (ref "MUX2") (pin "2") (pinfunction "CHAN7_2") (pintype "bidirectional"))
      (node (ref "X_2") (pin "4") (pinfunction "4_4") (pintype "passive"))
    )
    (net (code "111") (name "X_C8") (class "Default")
      (node (ref "MUX3") (pin "5") (pinfunction "CHAN4_5") (pintype "bidirectional"))
      (node (ref "X_3") (pin "1") (pinfunction "1_1") (pintype "passive"))
    )
    (net (code "112") (name "X_C9") (class "Default")
      (node (ref "MUX3") (pin "4") (pinfunction "CHAN5_4") (pintype "bidirectional"))
      (node (ref "X_3") (pin "2") (pinfunction "2_2") (pintype "passive"))
    )
    (net (code "113") (name "X_C10") (class "Default")
      (node (ref "MUX3") (pin "3") (pinfunction "CHAN6_3") (pintype "bidirectional"))
      (node (ref "X_3") (pin "3") (pinfunction "3_3") (pintype "passive"))
    )
    (net (code "114") (name "X_C11") (class "Default")
      (node (ref "MUX3") (pin "2") (pinfunction "CHAN7_2") (pintype "bidirectional"))
      (node (ref "X_3") (pin "4") (pinfunction "4_4") (pintype "passive"))
    )
    (net (code "115") (name "X_C12") (class "Default")
      (node (ref "MUX4") (pin "5") (pinfunction "CHAN4_5") (pintype "bidirectional"))
      (node (ref "X_4") (pin "1") (pinfunction "1_1") (pintype "passive"))
    )
    (net (code "116") (name "X_C13") (class "Default")
      (node (ref "MUX4") (pin "4") (pinfunction "CHAN5_4") (pintype "bidirectional"))
      (node (ref "X_4") (pin "2") (pinfunction "2_2") (pintype "passive"))
    )
    (net (code "117") (name "X_C14") (class "Default")
      (node (ref "MUX4") (pin "3") (pinfunction "CHAN6_3") (pintype "bidirectional"))
      (node (ref "X_4") (pin "3") (pinfunction "3_3") (pintype "passive"))
    )
    (net (code "118") (name "X_C15") (class "Default")
      (node (ref "MUX4") (pin "2") (pinfunction "CHAN7_2") (pintype "bidirectional"))
      (node (ref "X_4") (pin "4") (pinfunction "4_4") (pintype "passive"))
    )
    (net (code "119") (name "Y_C0") (class "Default")
      (node (ref "MUX1") (pin "23") (pinfunction "CHAN8_23") (pintype "bidirectional"))
      (node (ref "Y_1") (pin "1") (pinfunction "1_1") (pintype "passive"))
    )
    (net (code "120") (name "Y_C1") (class "Default")
      (node (ref "MUX1") (pin "22") (pinfunction "CHAN9_22") (pintype "bidirectional"))
      (node (ref "Y_1") (pin "2") (pinfunction "2_2") (pintype "passive"))
    )
    (net (code "121") (name "Y_C2") (class "Default")
      (node (ref "MUX1") (pin "21") (pinfunction "CHAN10_21") (pintype "bidirectional"))
      (node (ref "Y_1") (pin "3") (pinfunction "3_3") (pintype "passive"))
    )
    (net (code "122") (name "Y_C3") (class "Default")
      (node (ref "MUX1") (pin "20") (pinfunction "CHAN11_20") (pintype "bidirectional"))
      (node (ref "Y_1") (pin "4") (pinfunction "4_4") (pintype "passive"))
    )
    (net (code "123") (name "Y_C4") (class "Default")
      (node (ref "MUX2") (pin "23") (pinfunction "CHAN8_23") (pintype "bidirectional"))
      (node (ref "Y_2") (pin "1") (pinfunction "1_1") (pintype "passive"))
    )
    (net (code "124") (name "Y_C5") (class "Default")
      (node (ref "MUX2") (pin "22") (pinfunction "CHAN9_22") (pintype "bidirectional"))
      (node (ref "Y_2") (pin "2") (pinfunction "2_2") (pintype "passive"))
    )
    (net (code "125") (name "Y_C6") (class "Default")
      (node (ref "MUX2") (pin "21") (pinfunction "CHAN10_21") (pintype "bidirectional"))
      (node (ref "Y_2") (pin "3") (pinfunction "3_3") (pintype "passive"))
    )
    (net (code "126") (name "Y_C7") (class "Default")
      (node (ref "MUX2") (pin "20") (pinfunction "CHAN11_20") (pintype "bidirectional"))
      (node (ref "Y_2") (pin "4") (pinfunction "4_4") (pintype "passive"))
    )
    (net (code "127") (name "Y_C8") (class "Default")
      (node (ref "MUX3") (pin "23") (pinfunction "CHAN8_23") (pintype "bidirectional"))
      (node (ref "Y_3") (pin "1") (pinfunction "1_1") (pintype "passive"))
    )
    (net (code "128") (name "Y_C9") (class "Default")
      (node (ref "MUX3") (pin "22") (pinfunction "CHAN9_22") (pintype "bidirectional"))
      (node (ref "Y_3") (pin "2") (pinfunction "2_2") (pintype "passive"))
    )
    (net (code "129") (name "Y_C10") (class "Default")
      (node (ref "MUX3") (pin "21") (pinfunction "CHAN10_21") (pintype "bidirectional"))
      (node (ref "Y_3") (pin "3") (pinfunction "3_3") (pintype "passive"))
    )
    (net (code "130") (name "Y_C11") (class "Default")
      (node (ref "MUX3") (pin "20") (pinfunction "CHAN11_20") (pintype "bidirectional"))
      (node (ref "Y_3") (pin "4") (pinfunction "4_4") (pintype "passive"))
    )
    (net (code "131") (name "Y_C12") (class "Default")
      (node (ref "MUX4") (pin "23") (pinfunction "CHAN8_23") (pintype "bidirectional"))
      (node (ref "Y_4") (pin "1") (pinfunction "1_1") (pintype "passive"))
    )
    (net (code "132") (name "Y_C13") (class "Default")
      (node (ref "MUX4") (pin "22") (pinfunction "CHAN9_22") (pintype "bidirectional"))
      (node (ref "Y_4") (pin "2") (pinfunction "2_2") (pintype "passive"))
    )
    (net (code "133") (name "Y_C14") (class "Default")
      (node (ref "MUX4") (pin "21") (pinfunction "CHAN10_21") (pintype "bidirectional"))
      (node (ref "Y_4") (pin "3") (pinfunction "3_3") (pintype "passive"))
    )
    (net (code "134") (name "Y_C15") (class "Default")
      (node (ref "MUX4") (pin "20") (pinfunction "CHAN11_20") (pintype "bidirectional"))
      (node (ref "Y_4") (pin "4") (pinfunction "4_4") (pintype "passive"))
    )
    (net (code "135") (name "unconnected-(TEENSY++-16,PWM-PadC6)") (class "Default")
      (node (ref "TEENSY++") (pin "C6") (pinfunction "16,PWM_C6") (pintype "bidirectional"))
    )
    (net (code "136") (name "unconnected-(TEENSY++-18,INT6-PadE6)") (class "Default")
      (node (ref "TEENSY++") (pin "E6") (pinfunction "18,INT6_E6") (pintype "bidirectional"))
    )
    (net (code "137") (name "unconnected-(TEENSY++-19-PadE7)") (class "Default")
      (node (ref "TEENSY++") (pin "E7") (pinfunction "19_E7") (pintype "bidirectional"))
    )
    (net (code "138") (name "unconnected-(TEENSY++-24,PWM-PadB4)") (class "Default")
      (node (ref "TEENSY++") (pin "B4") (pinfunction "24,PWM_B4") (pintype "bidirectional"))
    )
    (net (code "139") (name "unconnected-(TEENSY++-27,PWM-PadB7)") (class "Default")
      (node (ref "TEENSY++") (pin "B7") (pinfunction "27,PWM_B7") (pintype "bidirectional"))
    )
    (net (code "140") (name "unconnected-(TEENSY++-36,INT4-PadE4)") (class "Default")
      (node (ref "TEENSY++") (pin "E4") (pinfunction "36,INT4_E4") (pintype "bidirectional"))
    )
    (net (code "141") (name "unconnected-(TEENSY++-37,INT5-PadE5)") (class "Default")
      (node (ref "TEENSY++") (pin "E5") (pinfunction "37,INT5_E5") (pintype "bidirectional"))
    )
    (net (code "142") (name "unconnected-(TEENSY++-38,A0-PadF0)") (class "Default")
      (node (ref "TEENSY++") (pin "F0") (pinfunction "38,A0_F0") (pintype "bidirectional"))
    )
    (net (code "143") (name "unconnected-(TEENSY++-39,A1-PadF1)") (class "Default")
      (node (ref "TEENSY++") (pin "F1") (pinfunction "39,A1_F1") (pintype "bidirectional"))
    )
    (net (code "144") (name "unconnected-(TEENSY++-40,A2-PadF2)") (class "Default")
      (node (ref "TEENSY++") (pin "F2") (pinfunction "40,A2_F2") (pintype "bidirectional"))
    )
    (net (code "145") (name "unconnected-(TEENSY++-43,A5-PadF5)") (class "Default")
      (node (ref "TEENSY++") (pin "F5") (pinfunction "43,A5_F5") (pintype "bidirectional"))
    )
    (net (code "146") (name "unconnected-(TEENSY++-44,A6-PadF6)") (class "Default")
      (node (ref "TEENSY++") (pin "F6") (pinfunction "44,A6_F6") (pintype "bidirectional"))
    )
    (net (code "147") (name "unconnected-(TEENSY++-45,A7-PadF7)") (class "Default")
      (node (ref "TEENSY++") (pin "F7") (pinfunction "45,A7_F7") (pintype "bidirectional"))
    )
    (net (code "148") (name "unconnected-(TEENSY++-AREF-PadREF)") (class "Default")
      (node (ref "TEENSY++") (pin "REF") (pinfunction "AREF_REF") (pintype "input"))
    )
    (net (code "149") (name "unconnected-(TEENSY++-Pad+5V)") (class "Default")
      (node (ref "TEENSY++") (pin "+5V") (pinfunction "+5V_+5V") (pintype "power_in"))
    )
    (net (code "150") (name "unconnected-(TEENSY++-_RST-PadRST)") (class "Default")
      (node (ref "TEENSY++") (pin "RST") (pinfunction "_RST_RST") (pintype "input"))
    )
  )
)
